# SCH_POC-DRV8835_2022-11-29.net
KiCad netlist of a schematic drawn in EasyEDA
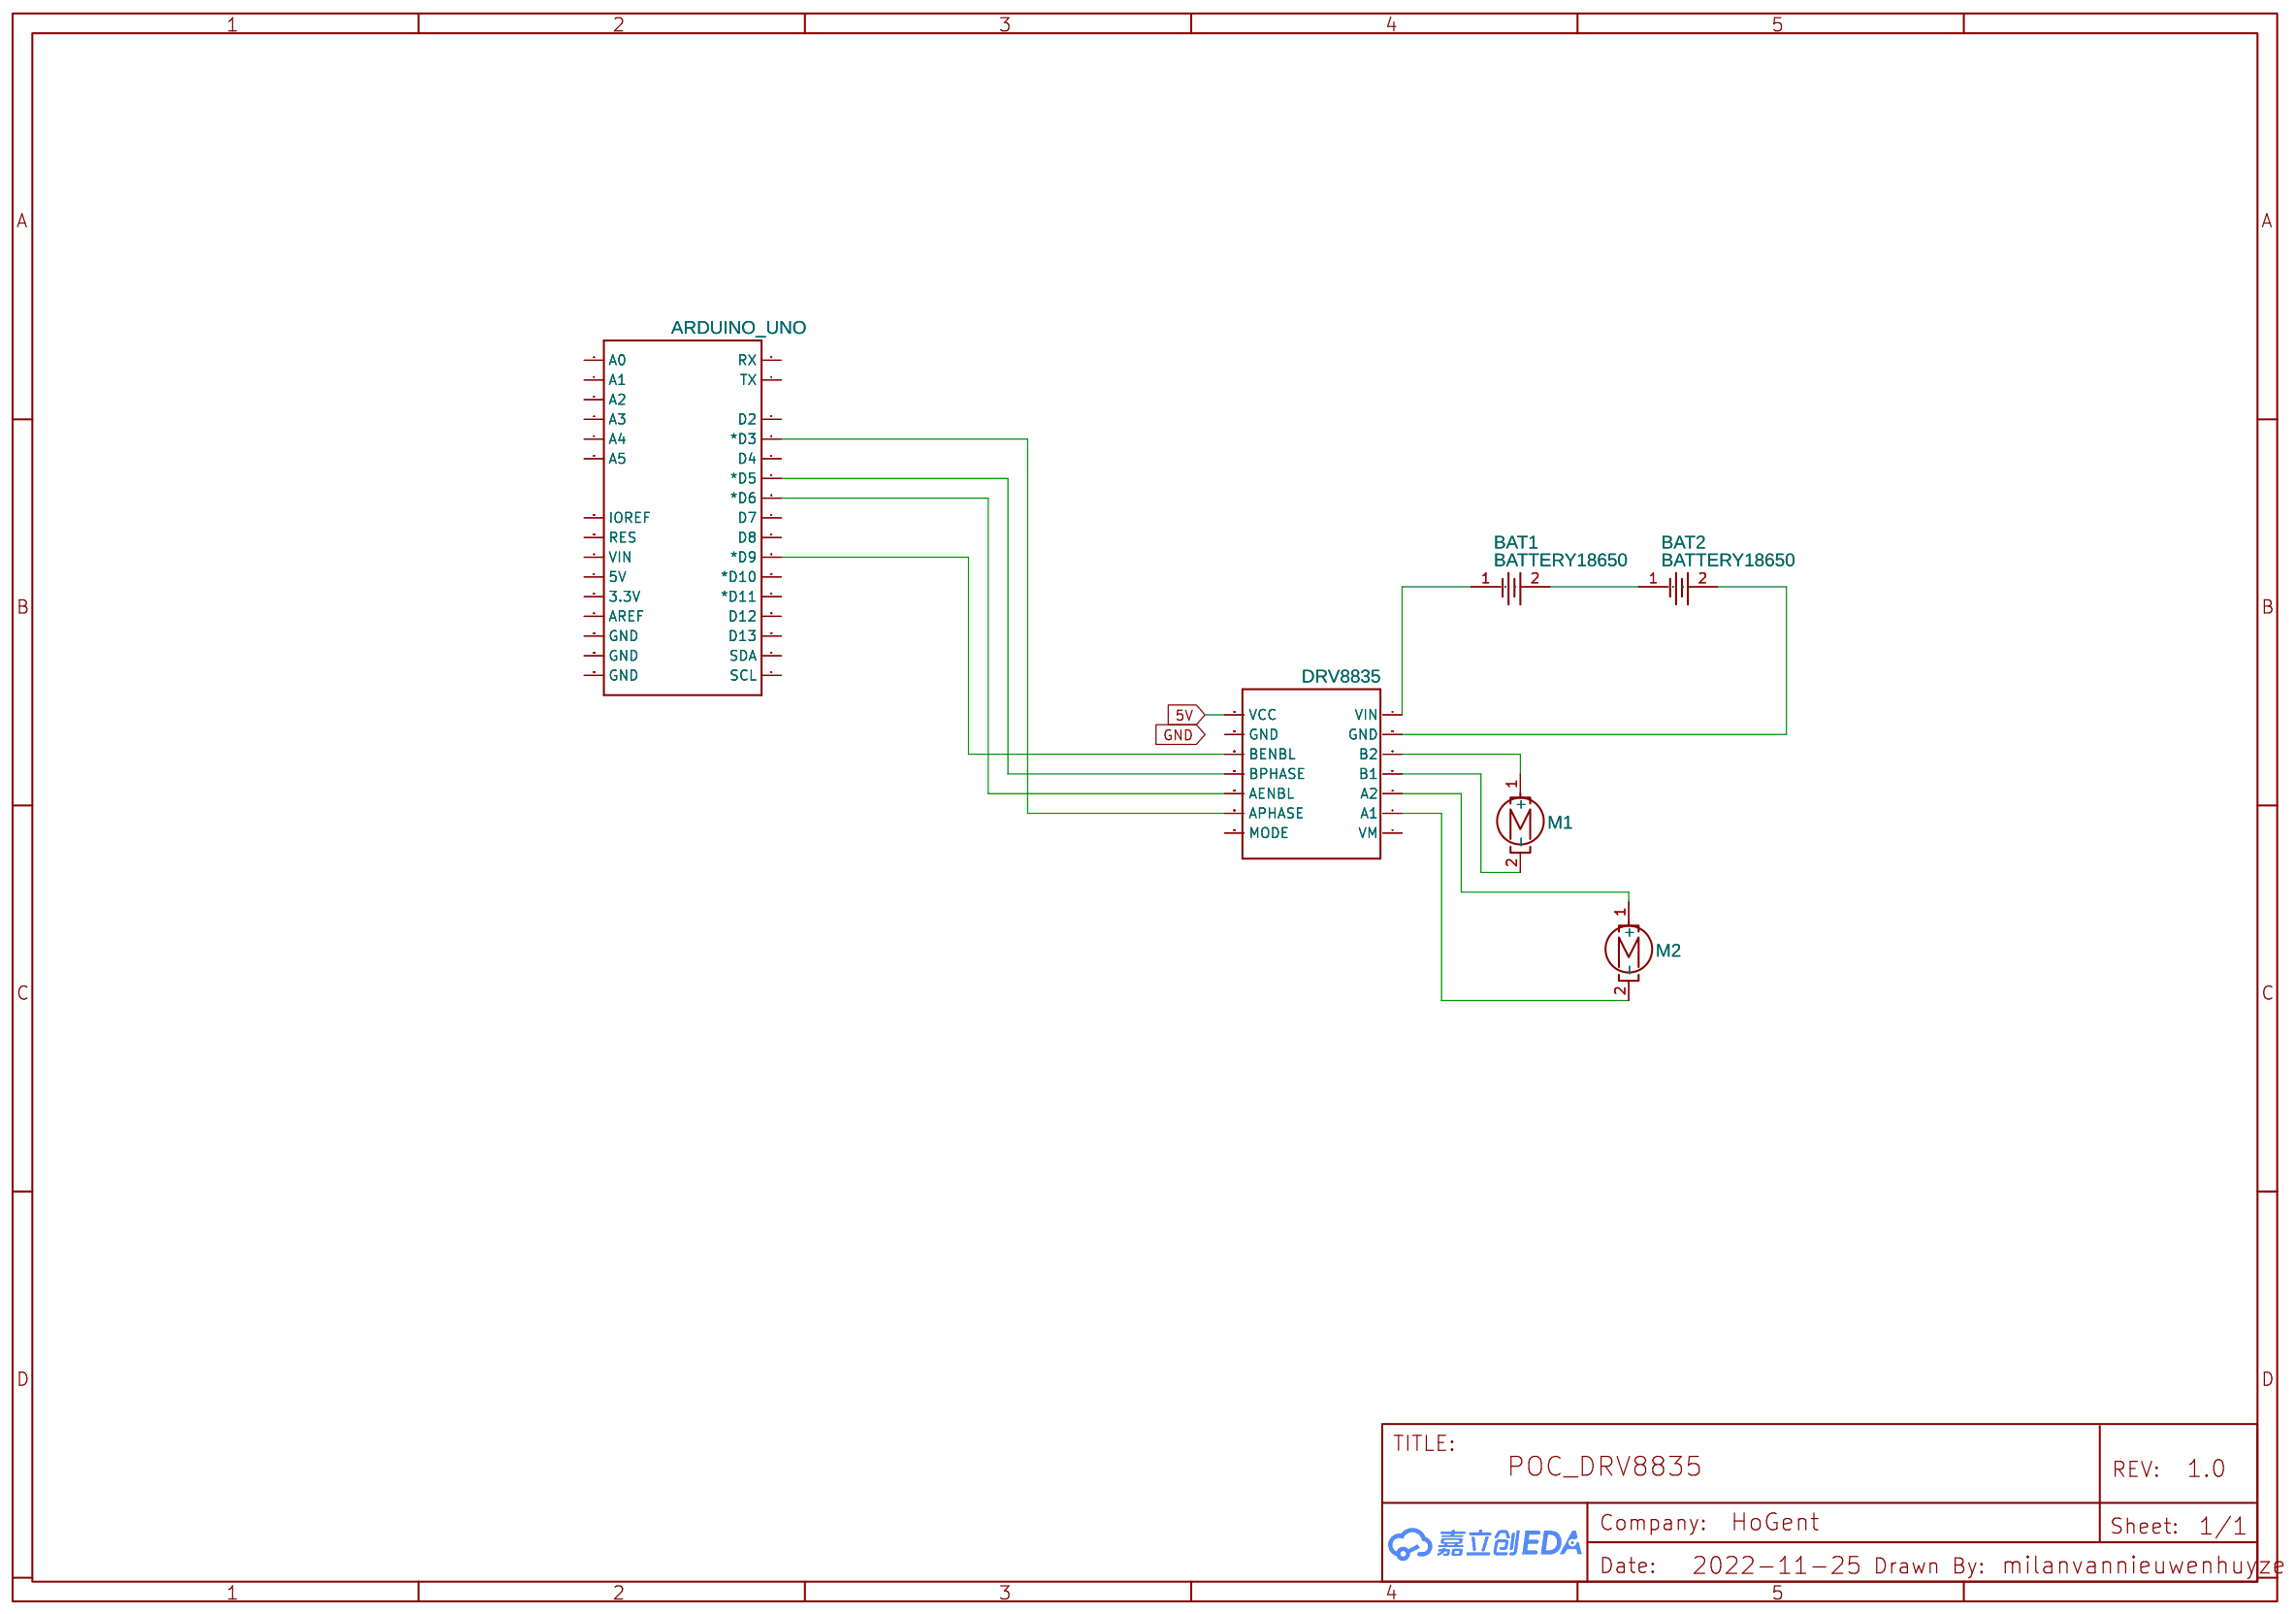
[diagram p0: schematic sheet]

(export (version "E")
  (design (tool "Eeschema 10.0.6"))
  (components
    (comp (ref "A2") (value "DRV8835") (libsource (lib "") (part "POLOLU_DRV8835")))
    (comp (ref "BAT1")
      (value "BATTERY18650")
      (fields
        (field (name "BOM_Manufacturer Part") "BH-18650-B1BA002")
        (field (name "BOM_Supplier Part") "C2988620")
      )
      (libsource (lib "") (part "BH-18650-B1BA002"))
    )
    (comp (ref "BAT2")
      (value "BATTERY18650")
      (fields
        (field (name "BOM_Manufacturer Part") "BH-18650-B1BA002")
        (field (name "BOM_Supplier Part") "C2988620")
      )
      (libsource (lib "") (part "BH-18650-B1BA002"))
    )
    (comp (ref "M1") (value "Motor_DC_ALT") (libsource (lib "") (part "Motor_DC_ALT")))
    (comp (ref "M2") (value "Motor_DC_ALT") (libsource (lib "") (part "Motor_DC_ALT")))
    (comp (ref "U1") (value "ARDUINO_UNO") (libsource (lib "") (part "ARDUINO_R3_SHIELD")))
  )
  (nets
    (net (code "1") (name "5V") (class "Default")
      (node (ref "A2") (pin "VCC") (pinfunction "VCC_VCC") (pintype "bidirectional"))
    )
    (net (code "3") (name "Net-(A2-GND-PadGND@2)") (class "Default")
      (node (ref "A2") (pin "GND@2") (pinfunction "GND_GND@2") (pintype "bidirectional"))
      (node (ref "BAT2") (pin "2") (pinfunction "2_2") (pintype "input"))
    )
    (net (code "4") (name "Net-(A2-PadVIN)") (class "Default")
      (node (ref "A2") (pin "VIN") (pinfunction "VIN_VIN") (pintype "bidirectional"))
      (node (ref "BAT1") (pin "1") (pinfunction "1_1") (pintype "input"))
    )
    (net (code "5") (name "Net-(BAT1-Pad2)") (class "Default")
      (node (ref "BAT1") (pin "2") (pinfunction "2_2") (pintype "input"))
      (node (ref "BAT2") (pin "1") (pinfunction "1_1") (pintype "input"))
    )
    (net (code "6") (name "Net-(M1-+)") (class "Default")
      (node (ref "A2") (pin "B2") (pinfunction "B2_B2") (pintype "bidirectional"))
      (node (ref "M1") (pin "1") (pinfunction "+_1") (pintype "unspecified"))
    )
    (net (code "7") (name "Net-(M1--)") (class "Default")
      (node (ref "A2") (pin "B1") (pinfunction "B1_B1") (pintype "bidirectional"))
      (node (ref "M1") (pin "2") (pinfunction "-_2") (pintype "unspecified"))
    )
    (net (code "8") (name "Net-(M2-+)") (class "Default")
      (node (ref "A2") (pin "A2") (pinfunction "A2_A2") (pintype "bidirectional"))
      (node (ref "M2") (pin "1") (pinfunction "+_1") (pintype "unspecified"))
    )
    (net (code "9") (name "Net-(M2--)") (class "Default")
      (node (ref "A2") (pin "A1") (pinfunction "A1_A1") (pintype "bidirectional"))
      (node (ref "M2") (pin "2") (pinfunction "-_2") (pintype "unspecified"))
    )
    (net (code "10") (name "Net-(U1-*D3)") (class "Default")
      (node (ref "A2") (pin "APHASE") (pinfunction "APHASE_APHASE") (pintype "bidirectional"))
      (node (ref "U1") (pin "D3") (pinfunction "*D3_D3") (pintype "unspecified"))
    )
    (net (code "11") (name "Net-(U1-*D5)") (class "Default")
      (node (ref "A2") (pin "BPHASE") (pinfunction "BPHASE_BPHASE") (pintype "bidirectional"))
      (node (ref "U1") (pin "D5") (pinfunction "*D5_D5") (pintype "unspecified"))
    )
    (net (code "12") (name "Net-(U1-*D6)") (class "Default")
      (node (ref "A2") (pin "AENBL") (pinfunction "AENBL_AENBL") (pintype "bidirectional"))
      (node (ref "U1") (pin "D6") (pinfunction "*D6_D6") (pintype "unspecified"))
    )
    (net (code "13") (name "Net-(U1-*D9)") (class "Default")
      (node (ref "A2") (pin "BENBL") (pinfunction "BENBL_BENBL") (pintype "bidirectional"))
      (node (ref "U1") (pin "D9") (pinfunction "*D9_D9") (pintype "unspecified"))
    )
    (net (code "14") (name "unconnected-(A2-GND-PadGND@1)") (class "Default")
      (node (ref "A2") (pin "GND@1") (pinfunction "GND_GND@1") (pintype "bidirectional"))
    )
    (net (code "15") (name "unconnected-(A2-PadMODE)") (class "Default")
      (node (ref "A2") (pin "MODE") (pinfunction "MODE_MODE") (pintype "bidirectional"))
    )
    (net (code "16") (name "unconnected-(A2-PadVM)") (class "Default")
      (node (ref "A2") (pin "VM") (pinfunction "VM_VM") (pintype "bidirectional"))
    )
    (net (code "17") (name "unconnected-(U1-*D10-PadD10)") (class "Default")
      (node (ref "U1") (pin "D10") (pinfunction "*D10_D10") (pintype "unspecified"))
    )
    (net (code "18") (name "unconnected-(U1-*D11-PadD11)") (class "Default")
      (node (ref "U1") (pin "D11") (pinfunction "*D11_D11") (pintype "unspecified"))
    )
    (net (code "19") (name "unconnected-(U1-GND-PadGND@0)") (class "Default")
      (node (ref "U1") (pin "GND@0") (pinfunction "GND_GND@0") (pintype "unspecified"))
    )
    (net (code "20") (name "unconnected-(U1-GND-PadGND@1)") (class "Default")
      (node (ref "U1") (pin "GND@1") (pinfunction "GND_GND@1") (pintype "unspecified"))
    )
    (net (code "21") (name "unconnected-(U1-GND-PadGND@2)") (class "Default")
      (node (ref "U1") (pin "GND@2") (pinfunction "GND_GND@2") (pintype "unspecified"))
    )
    (net (code "22") (name "unconnected-(U1-Pad3.3V)") (class "Default")
      (node (ref "U1") (pin "3.3V") (pinfunction "3.3V_3.3V") (pintype "unspecified"))
    )
    (net (code "23") (name "unconnected-(U1-Pad5V)") (class "Default")
      (node (ref "U1") (pin "5V") (pinfunction "5V_5V") (pintype "unspecified"))
    )
    (net (code "24") (name "unconnected-(U1-PadA0)") (class "Default")
      (node (ref "U1") (pin "A0") (pinfunction "A0_A0") (pintype "unspecified"))
    )
    (net (code "25") (name "unconnected-(U1-PadA1)") (class "Default")
      (node (ref "U1") (pin "A1") (pinfunction "A1_A1") (pintype "unspecified"))
    )
    (net (code "26") (name "unconnected-(U1-PadA2)") (class "Default")
      (node (ref "U1") (pin "A2") (pinfunction "A2_A2") (pintype "unspecified"))
    )
    (net (code "27") (name "unconnected-(U1-PadA3)") (class "Default")
      (node (ref "U1") (pin "A3") (pinfunction "A3_A3") (pintype "unspecified"))
    )
    (net (code "28") (name "unconnected-(U1-PadA4)") (class "Default")
      (node (ref "U1") (pin "A4") (pinfunction "A4_A4") (pintype "unspecified"))
    )
    (net (code "29") (name "unconnected-(U1-PadA5)") (class "Default")
      (node (ref "U1") (pin "A5") (pinfunction "A5_A5") (pintype "unspecified"))
    )
    (net (code "30") (name "unconnected-(U1-PadAREF)") (class "Default")
      (node (ref "U1") (pin "AREF") (pinfunction "AREF_AREF") (pintype "unspecified"))
    )
    (net (code "31") (name "unconnected-(U1-PadD2)") (class "Default")
      (node (ref "U1") (pin "D2") (pinfunction "D2_D2") (pintype "unspecified"))
    )
    (net (code "32") (name "unconnected-(U1-PadD4)") (class "Default")
      (node (ref "U1") (pin "D4") (pinfunction "D4_D4") (pintype "unspecified"))
    )
    (net (code "33") (name "unconnected-(U1-PadD7)") (class "Default")
      (node (ref "U1") (pin "D7") (pinfunction "D7_D7") (pintype "unspecified"))
    )
    (net (code "34") (name "unconnected-(U1-PadD8)") (class "Default")
      (node (ref "U1") (pin "D8") (pinfunction "D8_D8") (pintype "unspecified"))
    )
    (net (code "35") (name "unconnected-(U1-PadD12)") (class "Default")
      (node (ref "U1") (pin "D12") (pinfunction "D12_D12") (pintype "unspecified"))
    )
    (net (code "36") (name "unconnected-(U1-PadD13)") (class "Default")
      (node (ref "U1") (pin "D13") (pinfunction "D13_D13") (pintype "unspecified"))
    )
    (net (code "37") (name "unconnected-(U1-PadIOREF)") (class "Default")
      (node (ref "U1") (pin "IOREF") (pinfunction "IOREF_IOREF") (pintype "unspecified"))
    )
    (net (code "38") (name "unconnected-(U1-PadRES)") (class "Default")
      (node (ref "U1") (pin "RES") (pinfunction "RES_RES") (pintype "unspecified"))
    )
    (net (code "39") (name "unconnected-(U1-PadRX)") (class "Default")
      (node (ref "U1") (pin "RX") (pinfunction "RX_RX") (pintype "unspecified"))
    )
    (net (code "40") (name "unconnected-(U1-PadSCL)") (class "Default")
      (node (ref "U1") (pin "SCL") (pinfunction "SCL_SCL") (pintype "unspecified"))
    )
    (net (code "41") (name "unconnected-(U1-PadSDA)") (class "Default")
      (node (ref "U1") (pin "SDA") (pinfunction "SDA_SDA") (pintype "unspecified"))
    )
    (net (code "42") (name "unconnected-(U1-PadTX)") (class "Default")
      (node (ref "U1") (pin "TX") (pinfunction "TX_TX") (pintype "unspecified"))
    )
    (net (code "43") (name "unconnected-(U1-PadVIN)") (class "Default")
      (node (ref "U1") (pin "VIN") (pinfunction "VIN_VIN") (pintype "unspecified"))
    )
  )
)
